# stm32f0-qfp32-devboard.net
KiCad netlist of a schematic drawn in EAGLE
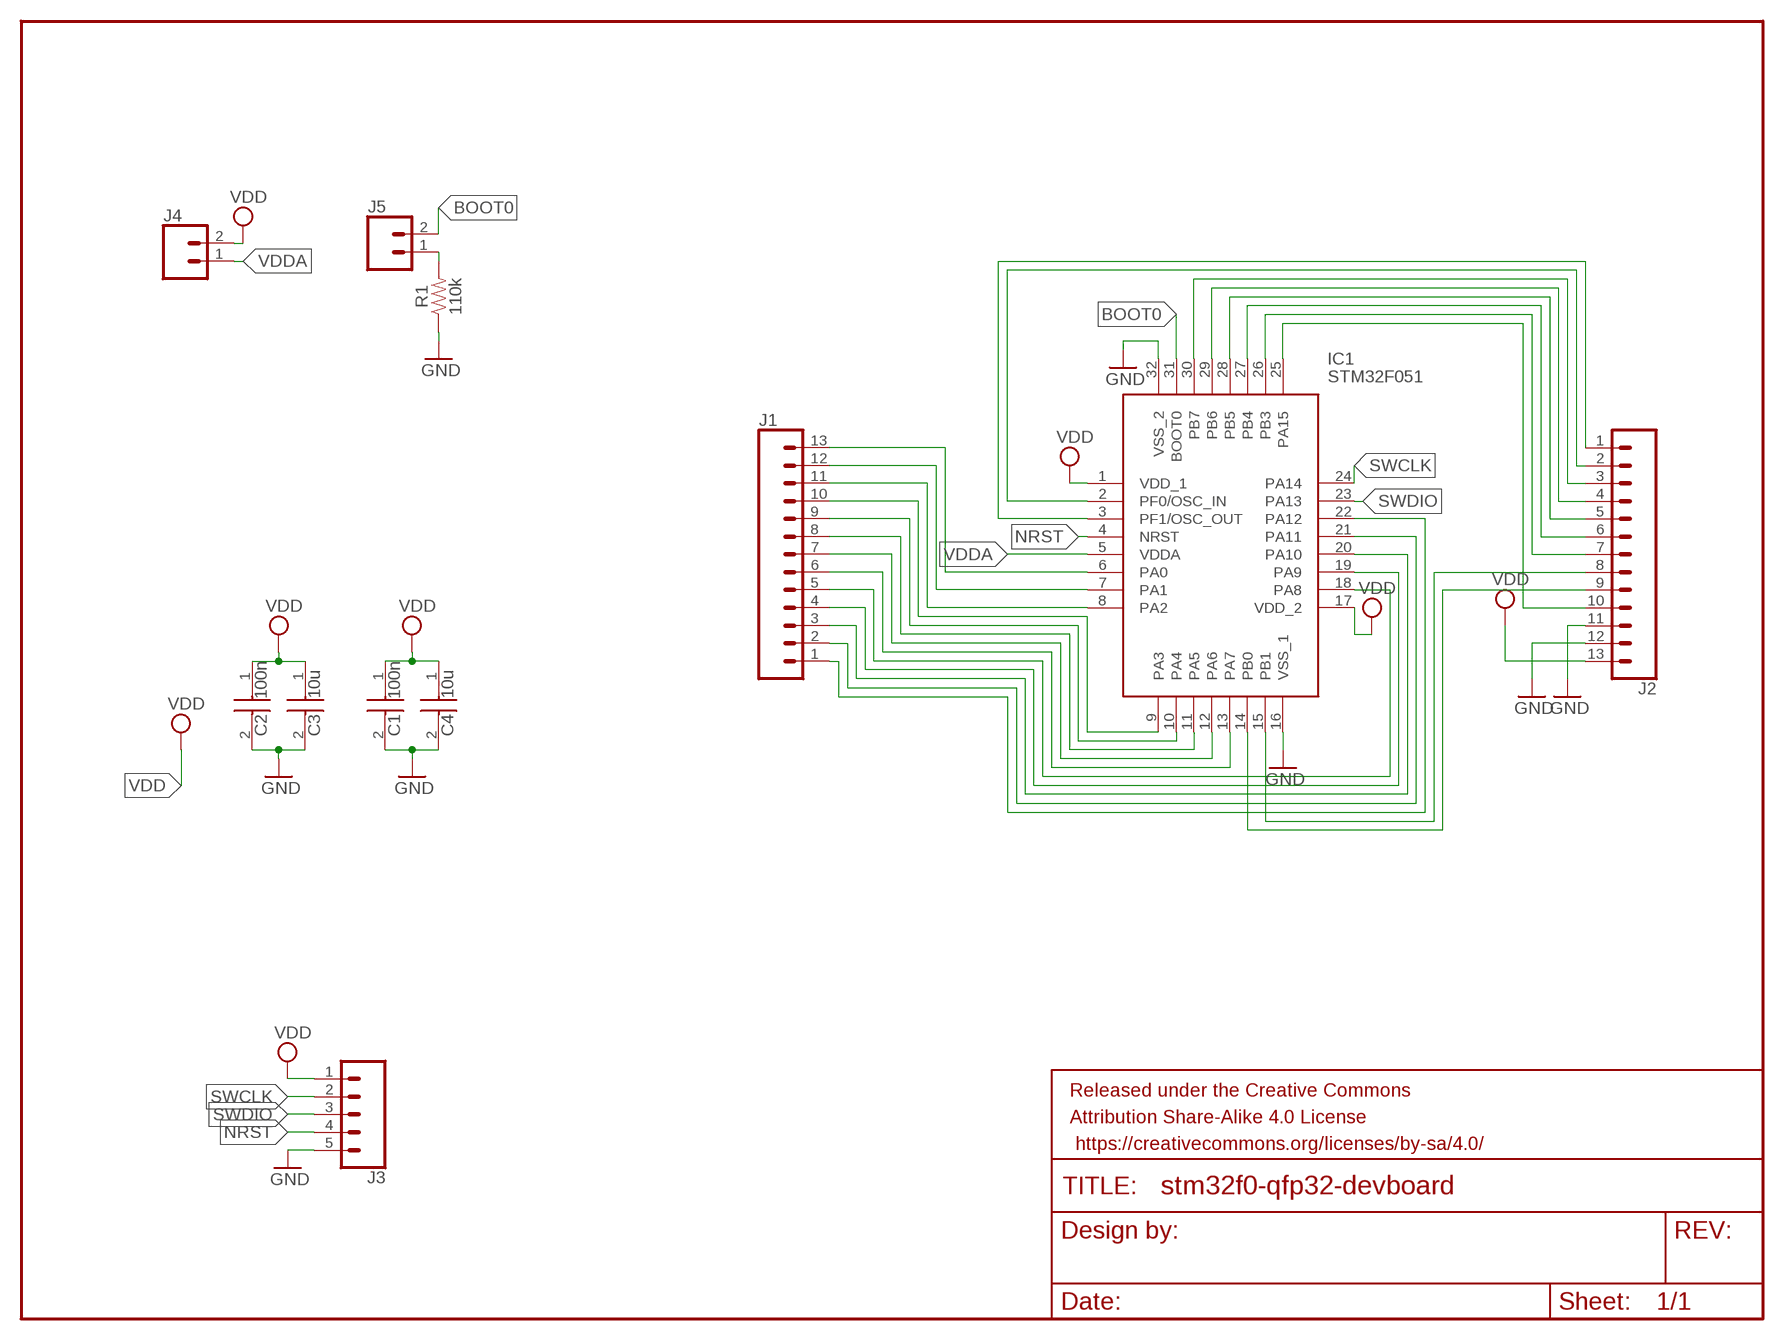
[diagram p0: schematic, sheet 1]

(export (version "E")
  (design (tool "Eeschema 10.0.6"))
  (components
    (comp (ref "C1")
      (value "100n")
      (footprint "eagle-import:CAPC2012X100N")
      (fields
        (field (name "MANUFACTURER_PART_NUMBER") "C2012X7R1H104K085AA")
        (field (name "MOUSER_PART_NUMBER") "810-C2012X7R1H104K-2")
      )
      (libsource (lib "eagle-import") (part "C2012X7R1H104K085AA"))
    )
    (comp (ref "C2")
      (value "100n")
      (footprint "eagle-import:CAPC2012X100N")
      (fields
        (field (name "MANUFACTURER_PART_NUMBER") "C2012X7R1H104K085AA")
        (field (name "MOUSER_PART_NUMBER") "810-C2012X7R1H104K-2")
      )
      (libsource (lib "eagle-import") (part "C2012X7R1H104K085AA"))
    )
    (comp (ref "C3")
      (value "10u")
      (footprint "eagle-import:CAPC3216X180N")
      (fields
        (field (name "MANUFACTURER_PART_NUMBER") "C3216X7R1C106K160AC")
        (field (name "MOUSER_PART_NUMBER") "810-C3216X7R1C106K")
      )
      (libsource (lib "eagle-import") (part "C3216X7R1C106K160AC"))
    )
    (comp (ref "C4")
      (value "10u")
      (footprint "eagle-import:CAPC3216X180N")
      (fields
        (field (name "MANUFACTURER_PART_NUMBER") "C3216X7R1C106K160AC")
        (field (name "MOUSER_PART_NUMBER") "810-C3216X7R1C106K")
      )
      (libsource (lib "eagle-import") (part "C3216X7R1C106K160AC"))
    )
    (comp (ref "FRAME2")
      (value "FRAME-LETTERNO_PACKAGE")
      (footprint "eagle-import:DUMMY")
      (fields (field (name "DESIGNER") "Nobody"))
      (libsource (lib "eagle-import") (part "FRAME-LETTERNO_PACKAGE"))
    )
    (comp (ref "IC1")
      (value "STM32F051")
      (footprint "eagle-import:QFP80P900X900X160-32N")
      (fields
        (field (name "MANUFACTURER_PART_NUMBER") "STM32F051K8T6")
        (field (name "MOUSER_PART_NUMBER") "511-STM32F051K8T6")
      )
      (libsource (lib "eagle-import") (part "STM32F051K8T6"))
    )
    (comp (ref "J1")
      (value "CONN_13")
      (footprint "eagle-import:1X13")
      (libsource (lib "eagle-import") (part "CONN_13"))
    )
    (comp (ref "J2")
      (value "CONN_13")
      (footprint "eagle-import:1X13")
      (libsource (lib "eagle-import") (part "CONN_13"))
    )
    (comp (ref "J3")
      (value "CONN_05")
      (footprint "eagle-import:1X05")
      (libsource (lib "eagle-import") (part "CONN_05"))
    )
    (comp (ref "J4")
      (value "CONN_02")
      (footprint "eagle-import:1X02")
      (libsource (lib "eagle-import") (part "CONN_02"))
    )
    (comp (ref "J5")
      (value "CONN_02")
      (footprint "eagle-import:1X02")
      (libsource (lib "eagle-import") (part "CONN_02"))
    )
    (comp (ref "R1")
      (value "110k")
      (footprint "eagle-import:0805")
      (libsource (lib "eagle-import") (part "0.22OHM-0805-1/4W-1%"))
    )
  )
  (nets
    (net (code "1") (name "BOOT0") (class "Default")
      (node (ref "IC1") (pin "31") (pinfunction "BOOT0_31") (pintype "bidirectional"))
      (node (ref "J5") (pin "2") (pinfunction "2_2") (pintype "passive"))
    )
    (net (code "2") (name "GND") (class "Default")
      (node (ref "C1") (pin "2") (pinfunction "2_2") (pintype "bidirectional"))
      (node (ref "C2") (pin "2") (pinfunction "2_2") (pintype "bidirectional"))
      (node (ref "C3") (pin "2") (pinfunction "2_2") (pintype "bidirectional"))
      (node (ref "C4") (pin "2") (pinfunction "2_2") (pintype "bidirectional"))
      (node (ref "IC1") (pin "16") (pinfunction "VSS_1_16") (pintype "power_in"))
      (node (ref "IC1") (pin "32") (pinfunction "VSS_2_32") (pintype "power_in"))
      (node (ref "J2") (pin "11") (pinfunction "11_11") (pintype "passive"))
      (node (ref "J2") (pin "12") (pinfunction "12_12") (pintype "passive"))
      (node (ref "J3") (pin "5") (pinfunction "5_5") (pintype "passive"))
      (node (ref "R1") (pin "1") (pinfunction "1_1") (pintype "passive"))
    )
    (net (code "3") (name "NRST") (class "Default")
      (node (ref "IC1") (pin "4") (pinfunction "NRST_4") (pintype "input"))
      (node (ref "J3") (pin "4") (pinfunction "4_4") (pintype "passive"))
    )
    (net (code "4") (name "Net-(IC1-PA0)") (class "Default")
      (node (ref "IC1") (pin "6") (pinfunction "PA0_6") (pintype "bidirectional"))
      (node (ref "J1") (pin "13") (pinfunction "13_13") (pintype "passive"))
    )
    (net (code "5") (name "Net-(IC1-PA1)") (class "Default")
      (node (ref "IC1") (pin "7") (pinfunction "PA1_7") (pintype "bidirectional"))
      (node (ref "J1") (pin "12") (pinfunction "12_12") (pintype "passive"))
    )
    (net (code "6") (name "Net-(IC1-PA2)") (class "Default")
      (node (ref "IC1") (pin "8") (pinfunction "PA2_8") (pintype "bidirectional"))
      (node (ref "J1") (pin "11") (pinfunction "11_11") (pintype "passive"))
    )
    (net (code "7") (name "Net-(IC1-PA3)") (class "Default")
      (node (ref "IC1") (pin "9") (pinfunction "PA3_9") (pintype "bidirectional"))
      (node (ref "J1") (pin "10") (pinfunction "10_10") (pintype "passive"))
    )
    (net (code "8") (name "Net-(IC1-PA4)") (class "Default")
      (node (ref "IC1") (pin "10") (pinfunction "PA4_10") (pintype "bidirectional"))
      (node (ref "J1") (pin "9") (pinfunction "9_9") (pintype "passive"))
    )
    (net (code "9") (name "Net-(IC1-PA5)") (class "Default")
      (node (ref "IC1") (pin "11") (pinfunction "PA5_11") (pintype "bidirectional"))
      (node (ref "J1") (pin "8") (pinfunction "8_8") (pintype "passive"))
    )
    (net (code "10") (name "Net-(IC1-PA6)") (class "Default")
      (node (ref "IC1") (pin "12") (pinfunction "PA6_12") (pintype "bidirectional"))
      (node (ref "J1") (pin "7") (pinfunction "7_7") (pintype "passive"))
    )
    (net (code "11") (name "Net-(IC1-PA7)") (class "Default")
      (node (ref "IC1") (pin "13") (pinfunction "PA7_13") (pintype "bidirectional"))
      (node (ref "J1") (pin "6") (pinfunction "6_6") (pintype "passive"))
    )
    (net (code "12") (name "Net-(IC1-PA8)") (class "Default")
      (node (ref "IC1") (pin "18") (pinfunction "PA8_18") (pintype "bidirectional"))
      (node (ref "J1") (pin "5") (pinfunction "5_5") (pintype "passive"))
    )
    (net (code "13") (name "Net-(IC1-PA9)") (class "Default")
      (node (ref "IC1") (pin "19") (pinfunction "PA9_19") (pintype "bidirectional"))
      (node (ref "J1") (pin "4") (pinfunction "4_4") (pintype "passive"))
    )
    (net (code "14") (name "Net-(IC1-PA10)") (class "Default")
      (node (ref "IC1") (pin "20") (pinfunction "PA10_20") (pintype "bidirectional"))
      (node (ref "J1") (pin "3") (pinfunction "3_3") (pintype "passive"))
    )
    (net (code "15") (name "Net-(IC1-PA11)") (class "Default")
      (node (ref "IC1") (pin "21") (pinfunction "PA11_21") (pintype "bidirectional"))
      (node (ref "J1") (pin "2") (pinfunction "2_2") (pintype "passive"))
    )
    (net (code "16") (name "Net-(IC1-PA12)") (class "Default")
      (node (ref "IC1") (pin "22") (pinfunction "PA12_22") (pintype "bidirectional"))
      (node (ref "J1") (pin "1") (pinfunction "1_1") (pintype "passive"))
    )
    (net (code "17") (name "Net-(IC1-PA15)") (class "Default")
      (node (ref "IC1") (pin "25") (pinfunction "PA15_25") (pintype "bidirectional"))
      (node (ref "J2") (pin "10") (pinfunction "10_10") (pintype "passive"))
    )
    (net (code "18") (name "Net-(IC1-PB0)") (class "Default")
      (node (ref "IC1") (pin "14") (pinfunction "PB0_14") (pintype "bidirectional"))
      (node (ref "J2") (pin "9") (pinfunction "9_9") (pintype "passive"))
    )
    (net (code "19") (name "Net-(IC1-PB1)") (class "Default")
      (node (ref "IC1") (pin "15") (pinfunction "PB1_15") (pintype "bidirectional"))
      (node (ref "J2") (pin "8") (pinfunction "8_8") (pintype "passive"))
    )
    (net (code "20") (name "Net-(IC1-PB3)") (class "Default")
      (node (ref "IC1") (pin "26") (pinfunction "PB3_26") (pintype "bidirectional"))
      (node (ref "J2") (pin "7") (pinfunction "7_7") (pintype "passive"))
    )
    (net (code "21") (name "Net-(IC1-PB4)") (class "Default")
      (node (ref "IC1") (pin "27") (pinfunction "PB4_27") (pintype "bidirectional"))
      (node (ref "J2") (pin "6") (pinfunction "6_6") (pintype "passive"))
    )
    (net (code "22") (name "Net-(IC1-PB5)") (class "Default")
      (node (ref "IC1") (pin "28") (pinfunction "PB5_28") (pintype "bidirectional"))
      (node (ref "J2") (pin "5") (pinfunction "5_5") (pintype "passive"))
    )
    (net (code "23") (name "Net-(IC1-PB6)") (class "Default")
      (node (ref "IC1") (pin "29") (pinfunction "PB6_29") (pintype "bidirectional"))
      (node (ref "J2") (pin "4") (pinfunction "4_4") (pintype "passive"))
    )
    (net (code "24") (name "Net-(IC1-PB7)") (class "Default")
      (node (ref "IC1") (pin "30") (pinfunction "PB7_30") (pintype "bidirectional"))
      (node (ref "J2") (pin "3") (pinfunction "3_3") (pintype "passive"))
    )
    (net (code "25") (name "Net-(IC1-PF0{slash}OSC_IN)") (class "Default")
      (node (ref "IC1") (pin "2") (pinfunction "PF0/OSC_IN_2") (pintype "input"))
      (node (ref "J2") (pin "2") (pinfunction "2_2") (pintype "passive"))
    )
    (net (code "26") (name "Net-(IC1-PF1{slash}OSC_OUT)") (class "Default")
      (node (ref "IC1") (pin "3") (pinfunction "PF1/OSC_OUT_3") (pintype "output"))
      (node (ref "J2") (pin "1") (pinfunction "1_1") (pintype "passive"))
    )
    (net (code "27") (name "Net-(J5-Pad1)") (class "Default")
      (node (ref "J5") (pin "1") (pinfunction "1_1") (pintype "passive"))
      (node (ref "R1") (pin "2") (pinfunction "2_2") (pintype "passive"))
    )
    (net (code "28") (name "SWCLK") (class "Default")
      (node (ref "IC1") (pin "24") (pinfunction "PA14_24") (pintype "bidirectional"))
      (node (ref "J3") (pin "2") (pinfunction "2_2") (pintype "passive"))
    )
    (net (code "29") (name "SWDIO") (class "Default")
      (node (ref "IC1") (pin "23") (pinfunction "PA13_23") (pintype "bidirectional"))
      (node (ref "J3") (pin "3") (pinfunction "3_3") (pintype "passive"))
    )
    (net (code "30") (name "VDD") (class "Default")
      (node (ref "C1") (pin "1") (pinfunction "1_1") (pintype "bidirectional"))
      (node (ref "C2") (pin "1") (pinfunction "1_1") (pintype "bidirectional"))
      (node (ref "C3") (pin "1") (pinfunction "1_1") (pintype "bidirectional"))
      (node (ref "C4") (pin "1") (pinfunction "1_1") (pintype "bidirectional"))
      (node (ref "IC1") (pin "1") (pinfunction "VDD_1_1") (pintype "power_in"))
      (node (ref "IC1") (pin "17") (pinfunction "VDD_2_17") (pintype "power_in"))
      (node (ref "J2") (pin "13") (pinfunction "13_13") (pintype "passive"))
      (node (ref "J3") (pin "1") (pinfunction "1_1") (pintype "passive"))
      (node (ref "J4") (pin "2") (pinfunction "2_2") (pintype "passive"))
    )
    (net (code "31") (name "VDDA") (class "Default")
      (node (ref "IC1") (pin "5") (pinfunction "VDDA_5") (pintype "power_in"))
      (node (ref "J4") (pin "1") (pinfunction "1_1") (pintype "passive"))
    )
  )
)
